# LED_Connectors.net
KiCad netlist of a schematic drawn in Altium Designer
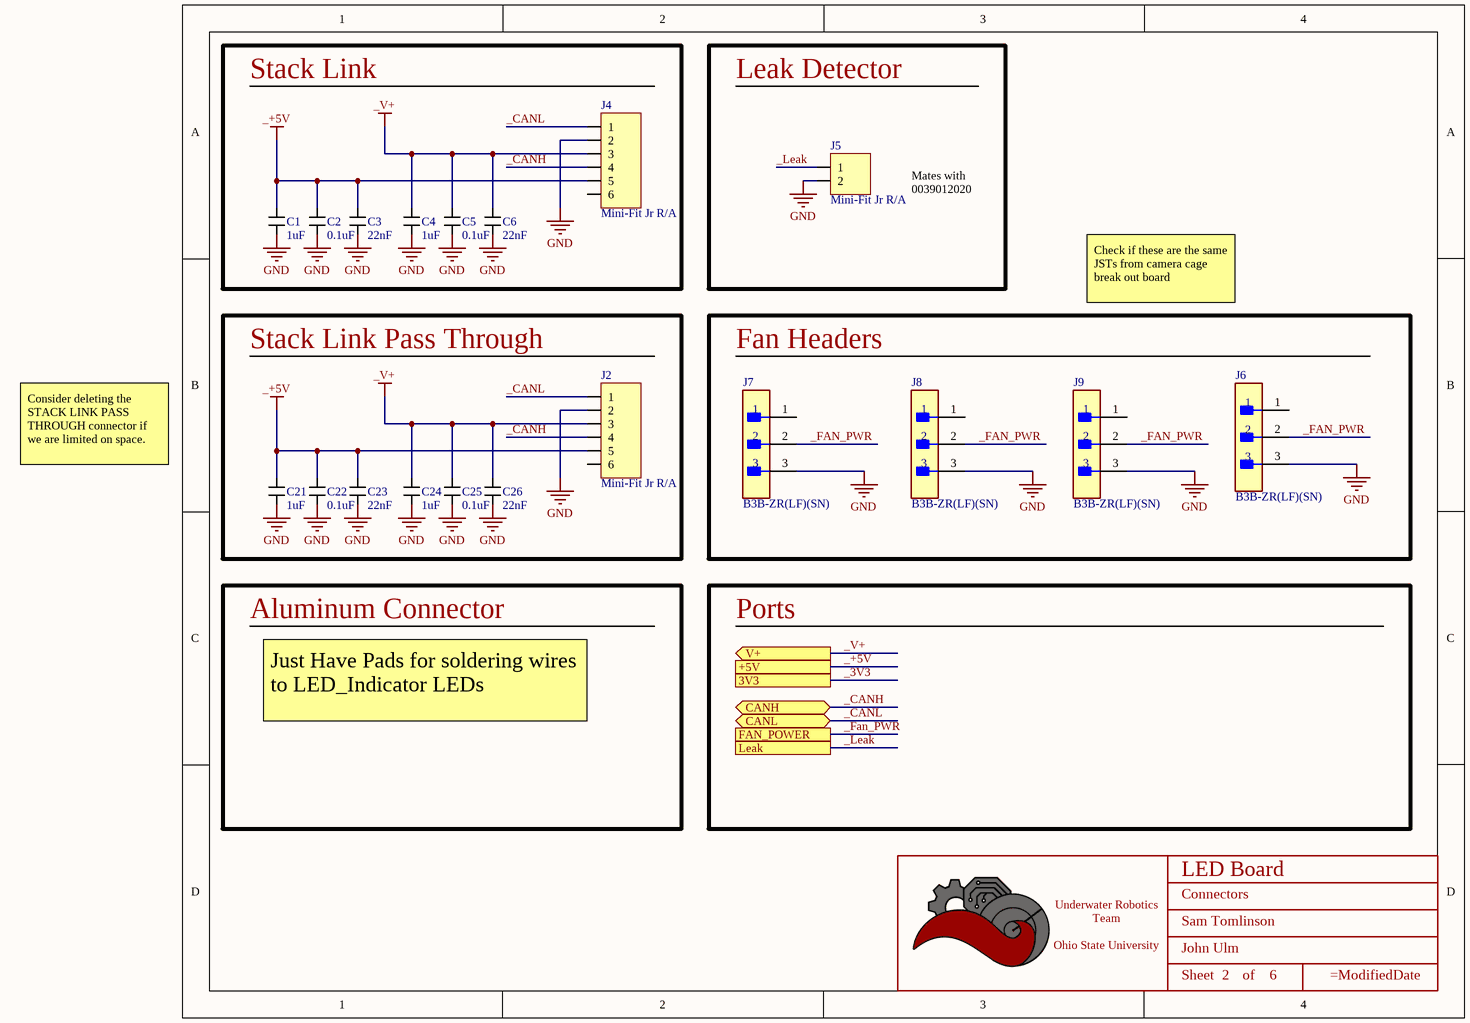
[diagram p0: LED_Connectors.SchDoc]

(export (version "E")
  (design (tool "Eeschema 10.0.6"))
  (components
    (comp (ref "C1")
      (value "1uF")
      (footprint "CAPACITOR_0603")
      (description "Cap 1uF 16V +/-10%\r\nCeramic 0603")
      (fields
        (field (name "TOLERANCE") "+/- 10%")
        (field (name "VOLTAGE") "16V")
        (field (name "MADE BY") "Flip B")
      )
      (libsource (lib "Capacitors") (part "CAPACITOR_1uF_0603"))
    )
    (comp (ref "C2")
      (value "0.1uF")
      (footprint "CAPACITOR_0805")
      (description "Cap 100nF 50V +/-10%\r\nCeramic 0805")
      (fields
        (field (name "TOLERANCE") "+/- 10%")
        (field (name "VOLTAGE") "50V")
        (field (name "MADE BY") "Robert Pafford")
      )
      (libsource (lib "Capacitors") (part "CAPACITOR_0.1uF_0805"))
    )
    (comp (ref "C3")
      (value "22nF")
      (footprint "CAPACITOR_0402")
      (description "Cap 22nF 25V +/-10%\r\nCeramic 0402")
      (fields
        (field (name "TOLERANCE") "+/- 10%")
        (field (name "VOLTAGE") "25V")
        (field (name "MADE BY") "Robert Pafford")
      )
      (libsource (lib "Capacitors") (part "CAPACITOR_0.022uF_0402"))
    )
    (comp (ref "C4")
      (value "1uF")
      (footprint "CAPACITOR_0603")
      (description "Cap 1uF 16V +/-10%\r\nCeramic 0603")
      (fields
        (field (name "TOLERANCE") "+/- 10%")
        (field (name "VOLTAGE") "16V")
        (field (name "MADE BY") "Flip B")
      )
      (libsource (lib "Capacitors") (part "CAPACITOR_1uF_0603"))
    )
    (comp (ref "C5")
      (value "0.1uF")
      (footprint "CAPACITOR_0805")
      (description "Cap 100nF 50V +/-10%\r\nCeramic 0805")
      (fields
        (field (name "TOLERANCE") "+/- 10%")
        (field (name "VOLTAGE") "50V")
        (field (name "MADE BY") "Robert Pafford")
      )
      (libsource (lib "Capacitors") (part "CAPACITOR_0.1uF_0805"))
    )
    (comp (ref "C6")
      (value "22nF")
      (footprint "CAPACITOR_0402")
      (description "Cap 22nF 25V +/-10%\r\nCeramic 0402")
      (fields
        (field (name "TOLERANCE") "+/- 10%")
        (field (name "VOLTAGE") "25V")
        (field (name "MADE BY") "Robert Pafford")
      )
      (libsource (lib "Capacitors") (part "CAPACITOR_0.022uF_0402"))
    )
    (comp (ref "C21")
      (value "1uF")
      (footprint "CAPACITOR_0603")
      (description "Cap 1uF 16V +/-10%\r\nCeramic 0603")
      (fields
        (field (name "TOLERANCE") "+/- 10%")
        (field (name "VOLTAGE") "16V")
        (field (name "MADE BY") "Flip B")
      )
      (libsource (lib "Capacitors") (part "CAPACITOR_1uF_0603"))
    )
    (comp (ref "C22")
      (value "0.1uF")
      (footprint "CAPACITOR_0805")
      (description "Cap 100nF 50V +/-10%\r\nCeramic 0805")
      (fields
        (field (name "TOLERANCE") "+/- 10%")
        (field (name "VOLTAGE") "50V")
        (field (name "MADE BY") "Robert Pafford")
      )
      (libsource (lib "Capacitors") (part "CAPACITOR_0.1uF_0805"))
    )
    (comp (ref "C23")
      (value "22nF")
      (footprint "CAPACITOR_0402")
      (description "Cap 22nF 25V +/-10%\r\nCeramic 0402")
      (fields
        (field (name "TOLERANCE") "+/- 10%")
        (field (name "VOLTAGE") "25V")
        (field (name "MADE BY") "Robert Pafford")
      )
      (libsource (lib "Capacitors") (part "CAPACITOR_0.022uF_0402"))
    )
    (comp (ref "C24")
      (value "1uF")
      (footprint "CAPACITOR_0603")
      (description "Cap 1uF 16V +/-10%\r\nCeramic 0603")
      (fields
        (field (name "TOLERANCE") "+/- 10%")
        (field (name "VOLTAGE") "16V")
        (field (name "MADE BY") "Flip B")
      )
      (libsource (lib "Capacitors") (part "CAPACITOR_1uF_0603"))
    )
    (comp (ref "C25")
      (value "0.1uF")
      (footprint "CAPACITOR_0805")
      (description "Cap 100nF 50V +/-10%\r\nCeramic 0805")
      (fields
        (field (name "TOLERANCE") "+/- 10%")
        (field (name "VOLTAGE") "50V")
        (field (name "MADE BY") "Robert Pafford")
      )
      (libsource (lib "Capacitors") (part "CAPACITOR_0.1uF_0805"))
    )
    (comp (ref "C26")
      (value "22nF")
      (footprint "CAPACITOR_0402")
      (description "Cap 22nF 25V +/-10%\r\nCeramic 0402")
      (fields
        (field (name "TOLERANCE") "+/- 10%")
        (field (name "VOLTAGE") "25V")
        (field (name "MADE BY") "Robert Pafford")
      )
      (libsource (lib "Capacitors") (part "CAPACITOR_0.022uF_0402"))
    )
    (comp (ref "J2")
      (value "Mini-Fit Jr R/A")
      (footprint "CONN_MOLEX_MINIFIT JR_6 POS_R/A")
      (description "Molex Minifit Jr. 5569 \r\n6 Pos R/A Natural")
      (fields (field (name "MANUFACTURER") "Molex") (field (name "CREATED BY") "Flip B"))
      (libsource (lib "Connectors") (part "CONN_MOLEX_MINIFIT JR_6POS_R/A"))
    )
    (comp (ref "J4")
      (value "Mini-Fit Jr R/A")
      (footprint "CONN_MOLEX_MINIFIT JR_6 POS_R/A")
      (description "Molex Minifit Jr. 5569 \r\n6 Pos R/A Natural")
      (fields (field (name "MANUFACTURER") "Molex") (field (name "CREATED BY") "Flip B"))
      (libsource (lib "Connectors") (part "CONN_MOLEX_MINIFIT JR_6POS_R/A"))
    )
    (comp (ref "J5")
      (value "Mini-Fit Jr R/A")
      (footprint "CONN_MOLEX_MINIFIT JR_2 POS_R/A")
      (description "Molex Minifit Jr. 5569 \r\n2 Pos R/A Natural")
      (fields (field (name "MANUFACTURER") "Molex") (field (name "CREATED BY") "Robert P"))
      (libsource (lib "Connectors") (part "CONN_MOLEX_MINIFIT JR_2POS_R/A"))
    )
    (comp (ref "J6")
      (value "B3B-ZR(LF)(SN)")
      (footprint "FP-B3B-ZR_LF_SN-MFG")
      (description "CONN HEADER VERT 3POS 1.5MM")
      (libsource (lib "Altium Content Vault") (part "0d3f023dd272f625e17a2be33dea85f"))
    )
    (comp (ref "J7")
      (value "B3B-ZR(LF)(SN)")
      (footprint "FP-B3B-ZR_LF_SN-MFG")
      (description "CONN HEADER VERT 3POS 1.5MM")
      (libsource (lib "Altium Content Vault") (part "0d3f023dd272f625e17a2be33dea85f"))
    )
    (comp (ref "J8")
      (value "B3B-ZR(LF)(SN)")
      (footprint "FP-B3B-ZR_LF_SN-MFG")
      (description "CONN HEADER VERT 3POS 1.5MM")
      (libsource (lib "Altium Content Vault") (part "0d3f023dd272f625e17a2be33dea85f"))
    )
    (comp (ref "J9")
      (value "B3B-ZR(LF)(SN)")
      (footprint "FP-B3B-ZR_LF_SN-MFG")
      (description "CONN HEADER VERT 3POS 1.5MM")
      (libsource (lib "Altium Content Vault") (part "0d3f023dd272f625e17a2be33dea85f"))
    )
  )
  (nets
    (net (code "2") (name "/_CANH") (class "Default")
      (node (ref "J2") (pin "4") (pinfunction "4_4") (pintype "passive"))
      (node (ref "J4") (pin "4") (pinfunction "4_4") (pintype "passive"))
    )
    (net (code "3") (name "/_CANL") (class "Default")
      (node (ref "J2") (pin "1") (pinfunction "1_1") (pintype "passive"))
      (node (ref "J4") (pin "1") (pinfunction "1_1") (pintype "passive"))
    )
    (net (code "4") (name "/_FAN_PWR") (class "Default")
      (node (ref "J6") (pin "2") (pinfunction "2_2") (pintype "passive"))
      (node (ref "J7") (pin "2") (pinfunction "2_2") (pintype "passive"))
      (node (ref "J8") (pin "2") (pinfunction "2_2") (pintype "passive"))
      (node (ref "J9") (pin "2") (pinfunction "2_2") (pintype "passive"))
    )
    (net (code "6") (name "/_Leak") (class "Default")
      (node (ref "J5") (pin "1") (pinfunction "1_1") (pintype "passive"))
    )
    (net (code "7") (name "GND") (class "Default")
      (node (ref "C1") (pin "2") (pinfunction "2_2") (pintype "passive"))
      (node (ref "C2") (pin "2") (pinfunction "2_2") (pintype "passive"))
      (node (ref "C21") (pin "2") (pinfunction "2_2") (pintype "passive"))
      (node (ref "C22") (pin "2") (pinfunction "2_2") (pintype "passive"))
      (node (ref "C23") (pin "2") (pinfunction "2_2") (pintype "passive"))
      (node (ref "C24") (pin "2") (pinfunction "2_2") (pintype "passive"))
      (node (ref "C25") (pin "2") (pinfunction "2_2") (pintype "passive"))
      (node (ref "C26") (pin "2") (pinfunction "2_2") (pintype "passive"))
      (node (ref "C3") (pin "2") (pinfunction "2_2") (pintype "passive"))
      (node (ref "C4") (pin "2") (pinfunction "2_2") (pintype "passive"))
      (node (ref "C5") (pin "2") (pinfunction "2_2") (pintype "passive"))
      (node (ref "C6") (pin "2") (pinfunction "2_2") (pintype "passive"))
      (node (ref "J2") (pin "2") (pinfunction "2_2") (pintype "passive"))
      (node (ref "J4") (pin "2") (pinfunction "2_2") (pintype "passive"))
      (node (ref "J5") (pin "2") (pinfunction "2_2") (pintype "passive"))
      (node (ref "J6") (pin "3") (pinfunction "3_3") (pintype "passive"))
      (node (ref "J7") (pin "3") (pinfunction "3_3") (pintype "passive"))
      (node (ref "J8") (pin "3") (pinfunction "3_3") (pintype "passive"))
      (node (ref "J9") (pin "3") (pinfunction "3_3") (pintype "passive"))
    )
    (net (code "8") (name "_+5V") (class "Default")
      (node (ref "C1") (pin "1") (pinfunction "1_1") (pintype "passive"))
      (node (ref "C2") (pin "1") (pinfunction "1_1") (pintype "passive"))
      (node (ref "C21") (pin "1") (pinfunction "1_1") (pintype "passive"))
      (node (ref "C22") (pin "1") (pinfunction "1_1") (pintype "passive"))
      (node (ref "C23") (pin "1") (pinfunction "1_1") (pintype "passive"))
      (node (ref "C3") (pin "1") (pinfunction "1_1") (pintype "passive"))
      (node (ref "J2") (pin "5") (pinfunction "5_5") (pintype "passive"))
      (node (ref "J4") (pin "5") (pinfunction "5_5") (pintype "passive"))
    )
    (net (code "9") (name "_V+") (class "Default")
      (node (ref "C24") (pin "1") (pinfunction "1_1") (pintype "passive"))
      (node (ref "C25") (pin "1") (pinfunction "1_1") (pintype "passive"))
      (node (ref "C26") (pin "1") (pinfunction "1_1") (pintype "passive"))
      (node (ref "C4") (pin "1") (pinfunction "1_1") (pintype "passive"))
      (node (ref "C5") (pin "1") (pinfunction "1_1") (pintype "passive"))
      (node (ref "C6") (pin "1") (pinfunction "1_1") (pintype "passive"))
      (node (ref "J2") (pin "3") (pinfunction "3_3") (pintype "passive"))
      (node (ref "J4") (pin "3") (pinfunction "3_3") (pintype "passive"))
    )
    (net (code "10") (name "unconnected-(J2-Pad6)") (class "Default")
      (node (ref "J2") (pin "6") (pinfunction "6_6") (pintype "passive"))
    )
    (net (code "11") (name "unconnected-(J4-Pad6)") (class "Default")
      (node (ref "J4") (pin "6") (pinfunction "6_6") (pintype "passive"))
    )
    (net (code "12") (name "unconnected-(J6-Pad1)") (class "Default")
      (node (ref "J6") (pin "1") (pinfunction "1_1") (pintype "passive"))
    )
    (net (code "13") (name "unconnected-(J7-Pad1)") (class "Default")
      (node (ref "J7") (pin "1") (pinfunction "1_1") (pintype "passive"))
    )
    (net (code "14") (name "unconnected-(J8-Pad1)") (class "Default")
      (node (ref "J8") (pin "1") (pinfunction "1_1") (pintype "passive"))
    )
    (net (code "15") (name "unconnected-(J9-Pad1)") (class "Default")
      (node (ref "J9") (pin "1") (pinfunction "1_1") (pintype "passive"))
    )
  )
)
